# CNC-MainStepInterface-panel.net
KiCad netlist of a schematic drawn in EAGLE
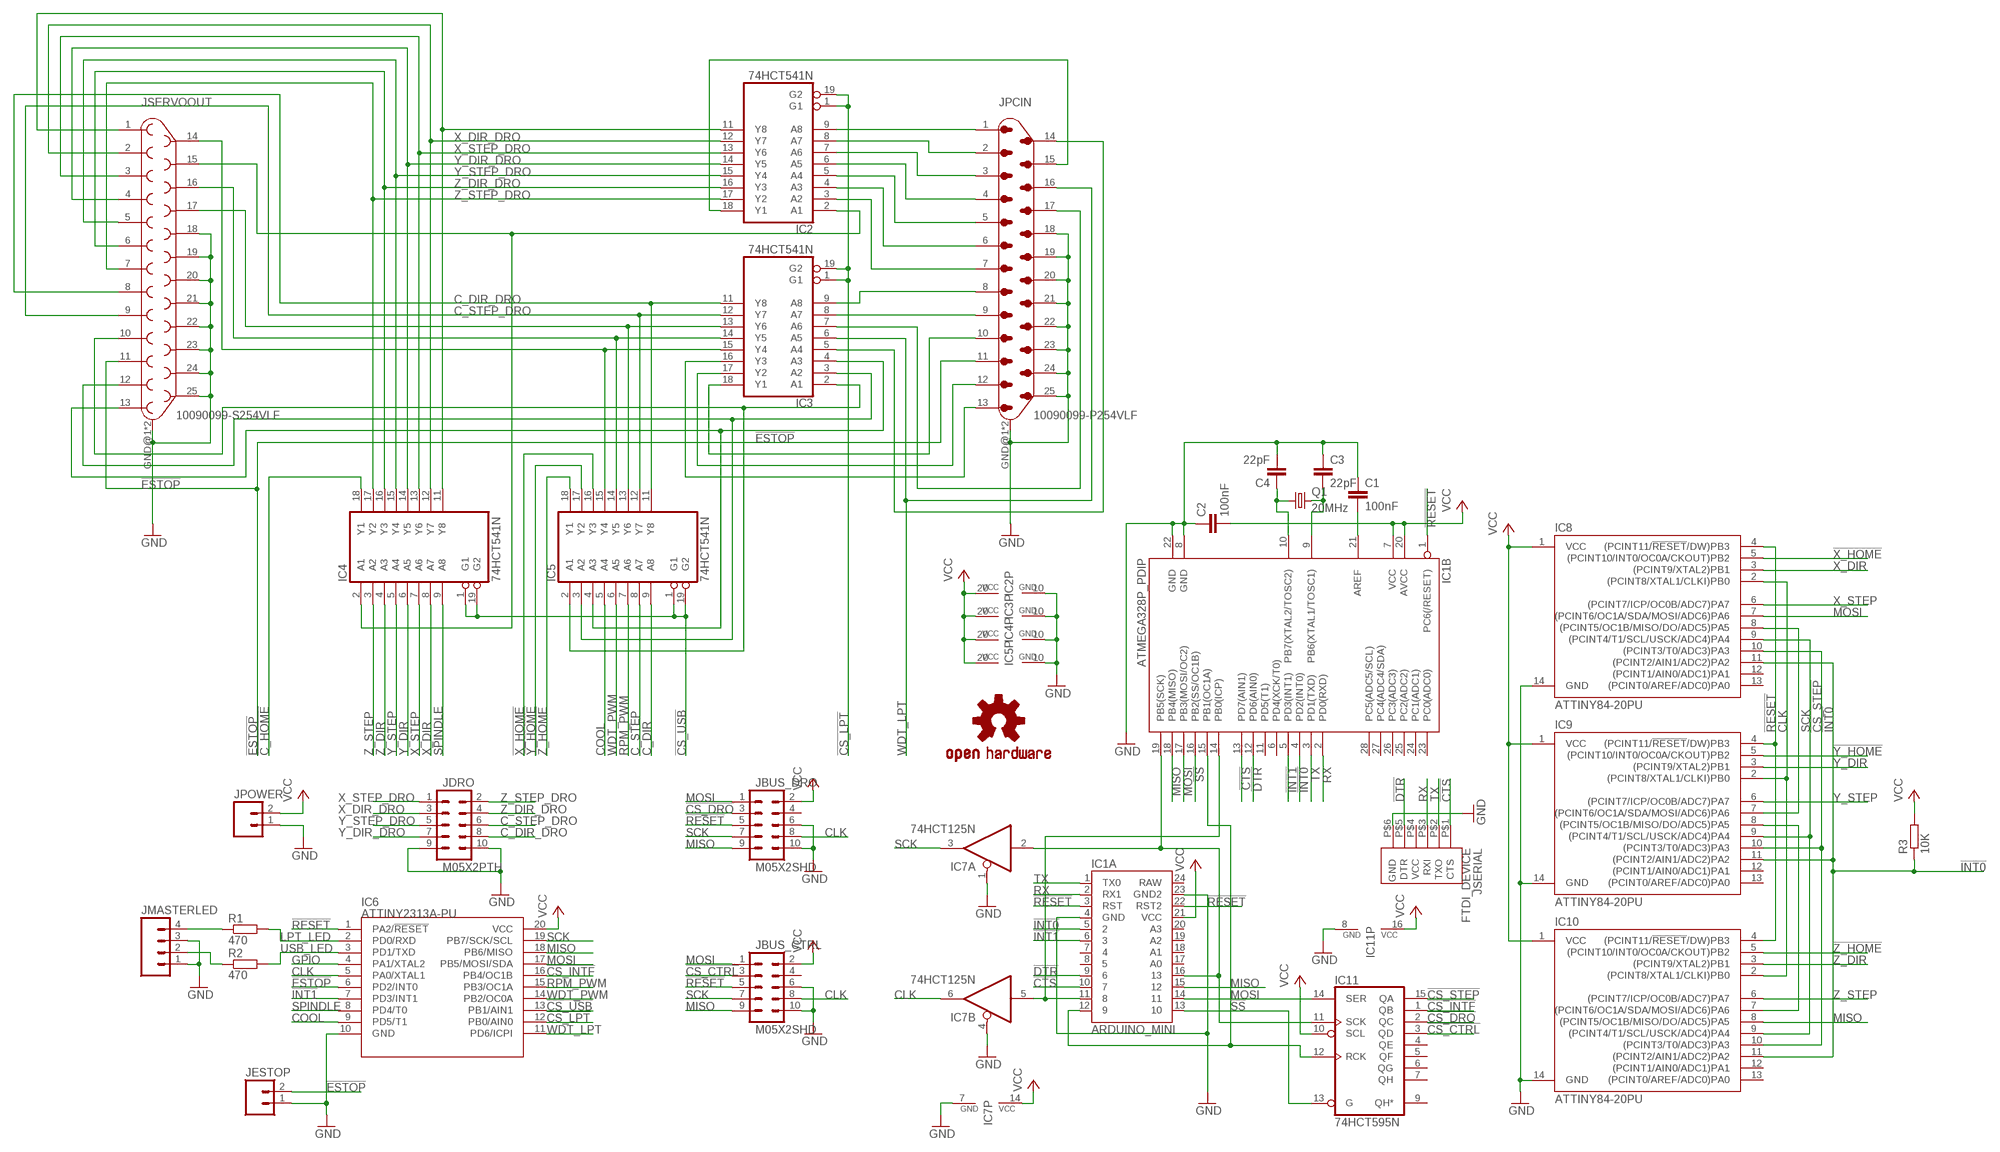
[diagram p0: schematic, sheet 1]

(export (version "E")
  (design (tool "Eeschema 10.0.6"))
  (components
    (comp (ref "C1")
      (value "100nF")
      (footprint "eagle-import:C050-025X075")
      (libsource (lib "eagle-import") (part "C-EU050-025X075"))
    )
    (comp (ref "C2")
      (value "100nF")
      (footprint "eagle-import:C050-025X075")
      (libsource (lib "eagle-import") (part "C-EU050-025X075"))
    )
    (comp (ref "C3")
      (value "22pF")
      (footprint "eagle-import:C050-025X075")
      (libsource (lib "eagle-import") (part "C-EU050-025X075"))
    )
    (comp (ref "C4")
      (value "22pF")
      (footprint "eagle-import:C050-025X075")
      (libsource (lib "eagle-import") (part "C-EU050-025X075"))
    )
    (comp (ref "IC1A")
      (value "ARDUINO_MINI")
      (footprint "eagle-import:ARDUINO_MINI")
      (libsource (lib "eagle-import") (part "ARDUINO_MINI"))
    )
    (comp (ref "IC1B")
      (value "ATMEGA328P_PDIP")
      (footprint "eagle-import:DIL28-3")
      (libsource (lib "eagle-import") (part "ATMEGA328P_PDIP"))
    )
    (comp (ref "IC2")
      (value "74HCT541N")
      (footprint "eagle-import:DIL20")
      (libsource (lib "eagle-import") (part "74541NHCT"))
    )
    (comp (ref "IC3")
      (value "74HCT541N")
      (footprint "eagle-import:DIL20")
      (libsource (lib "eagle-import") (part "74541NHCT"))
    )
    (comp (ref "IC4")
      (value "74HCT541N")
      (footprint "eagle-import:DIL20")
      (libsource (lib "eagle-import") (part "74541NHCT"))
    )
    (comp (ref "IC5")
      (value "74HCT541N")
      (footprint "eagle-import:DIL20")
      (libsource (lib "eagle-import") (part "74541NHCT"))
    )
    (comp (ref "IC6")
      (value "ATTINY2313A-PU")
      (footprint "eagle-import:DIL20")
      (libsource (lib "eagle-import") (part "ATTINY2313A-PU"))
    )
    (comp (ref "IC7")
      (value "74HCT125N")
      (footprint "eagle-import:DIL14")
      (libsource (lib "eagle-import") (part "74125NHCT"))
    )
    (comp (ref "IC8")
      (value "ATTINY84-20PU")
      (footprint "eagle-import:DIL14")
      (libsource (lib "eagle-import") (part "ATTINY84PU-20"))
    )
    (comp (ref "IC9")
      (value "ATTINY84-20PU")
      (footprint "eagle-import:DIL14")
      (libsource (lib "eagle-import") (part "ATTINY84PU-20"))
    )
    (comp (ref "IC10")
      (value "ATTINY84-20PU")
      (footprint "eagle-import:DIL14")
      (libsource (lib "eagle-import") (part "ATTINY84PU-20"))
    )
    (comp (ref "IC11")
      (value "74HCT595N")
      (footprint "eagle-import:DIL16")
      (libsource (lib "eagle-import") (part "74595NHCT"))
    )
    (comp (ref "JBUS_CTRL")
      (value "M05X2SHD")
      (footprint "eagle-import:2X5-SHROUDED")
      (libsource (lib "eagle-import") (part "M05X2SHD"))
    )
    (comp (ref "JBUS_DRO")
      (value "M05X2SHD")
      (footprint "eagle-import:2X5-SHROUDED")
      (libsource (lib "eagle-import") (part "M05X2SHD"))
    )
    (comp (ref "JDRO")
      (value "M05X2PTH")
      (footprint "eagle-import:AVR_ICSP")
      (libsource (lib "eagle-import") (part "M05X2PTH"))
    )
    (comp (ref "JESTOP")
      (value "M02PTH")
      (footprint "eagle-import:1X02")
      (libsource (lib "eagle-import") (part "M02PTH"))
    )
    (comp (ref "JMASTERLED")
      (value "M04PTH")
      (footprint "eagle-import:1X04")
      (libsource (lib "eagle-import") (part "M04PTH"))
    )
    (comp (ref "JPCIN")
      (value "10090099-P254VLF")
      (footprint "eagle-import:10090099-P254VLF")
      (libsource (lib "eagle-import") (part "10090099-P254VLF"))
    )
    (comp (ref "JPOWER")
      (value "M02POLAR")
      (footprint "eagle-import:MOLEX-1X2")
      (libsource (lib "eagle-import") (part "M02POLAR"))
    )
    (comp (ref "JSERIAL")
      (value "FTDI_DEVICE")
      (footprint "eagle-import:FTDI_DEVICE_SIDE")
      (libsource (lib "eagle-import") (part "FTDI_DEVICE"))
    )
    (comp (ref "JSERVOOUT")
      (value "10090099-S254VLF")
      (footprint "eagle-import:10090099-S254VLF")
      (libsource (lib "eagle-import") (part "10090099-S254VLF"))
    )
    (comp (ref "Q1")
      (value "20MHz")
      (footprint "eagle-import:HC49U-V")
      (libsource (lib "eagle-import") (part "CRYSTALHC49U-V"))
    )
    (comp (ref "R1")
      (value "470")
      (footprint "eagle-import:0207_10")
      (libsource (lib "eagle-import") (part "R-EU_0207/10"))
    )
    (comp (ref "R2")
      (value "470")
      (footprint "eagle-import:0207_10")
      (libsource (lib "eagle-import") (part "R-EU_0207/10"))
    )
    (comp (ref "R3")
      (value "10K")
      (footprint "eagle-import:0207_10")
      (libsource (lib "eagle-import") (part "R-EU_0207/10"))
    )
    (comp (ref "U$1")
      (value "SPARKFUN_OSHW-LOGOL")
      (footprint "eagle-import:SPARKFUN_OSHW-LOGO-L")
      (libsource (lib "eagle-import") (part "SPARKFUN_OSHW-LOGOL"))
    )
  )
  (nets
    (net (code "1") (name "/CLK") (class "Default")
      (node (ref "IC10") (pin "2") (pinfunction "(PCINT8/XTAL1/CLKI)PB0_2") (pintype "bidirectional"))
      (node (ref "IC6") (pin "5") (pinfunction "PA0/XTAL1_5") (pintype "bidirectional"))
      (node (ref "IC7") (pin "6") (pinfunction "O_6") (pintype "tri_state"))
      (node (ref "IC8") (pin "2") (pinfunction "(PCINT8/XTAL1/CLKI)PB0_2") (pintype "bidirectional"))
      (node (ref "IC9") (pin "2") (pinfunction "(PCINT8/XTAL1/CLKI)PB0_2") (pintype "bidirectional"))
      (node (ref "JBUS_CTRL") (pin "8") (pinfunction "8_8") (pintype "passive"))
      (node (ref "JBUS_DRO") (pin "8") (pinfunction "8_8") (pintype "passive"))
    )
    (net (code "2") (name "/COOL") (class "Default")
      (node (ref "IC5") (pin "5") (pinfunction "A4_5") (pintype "input"))
      (node (ref "IC6") (pin "9") (pinfunction "PD5/T1_9") (pintype "bidirectional"))
    )
    (net (code "3") (name "/C_DIR") (class "Default")
      (node (ref "IC5") (pin "9") (pinfunction "A8_9") (pintype "input"))
    )
    (net (code "4") (name "/C_DIR_DRO") (class "Default")
      (node (ref "IC3") (pin "11") (pinfunction "Y8_11") (pintype "tri_state"))
      (node (ref "IC5") (pin "11") (pinfunction "Y8_11") (pintype "tri_state"))
      (node (ref "JDRO") (pin "8") (pinfunction "8_8") (pintype "passive"))
      (node (ref "JSERVOOUT") (pin "8") (pinfunction "8_8") (pintype "passive"))
    )
    (net (code "5") (name "/C_STEP") (class "Default")
      (node (ref "IC5") (pin "8") (pinfunction "A7_8") (pintype "input"))
    )
    (net (code "6") (name "/C_STEP_DRO") (class "Default")
      (node (ref "IC3") (pin "12") (pinfunction "Y7_12") (pintype "tri_state"))
      (node (ref "IC5") (pin "12") (pinfunction "Y7_12") (pintype "tri_state"))
      (node (ref "JDRO") (pin "6") (pinfunction "6_6") (pintype "passive"))
      (node (ref "JSERVOOUT") (pin "9") (pinfunction "9_9") (pintype "passive"))
    )
    (net (code "7") (name "/GPIO") (class "Default")
      (node (ref "IC6") (pin "4") (pinfunction "PA1/XTAL2_4") (pintype "bidirectional"))
    )
    (net (code "8") (name "/LPT_LED") (class "Default")
      (node (ref "IC6") (pin "2") (pinfunction "PD0/RXD_2") (pintype "bidirectional"))
      (node (ref "R1") (pin "2") (pinfunction "2_2") (pintype "passive"))
    )
    (net (code "9") (name "/MISO") (class "Default")
      (node (ref "IC10") (pin "8") (pinfunction "(PCINT5/OC1B/MISO/DO/ADC5)PA5_8") (pintype "bidirectional"))
      (node (ref "IC1A") (pin "15") (pinfunction "12_15") (pintype "bidirectional"))
      (node (ref "IC1B") (pin "18") (pinfunction "PB4(MISO)_18") (pintype "bidirectional"))
      (node (ref "IC6") (pin "18") (pinfunction "PB6/MISO_18") (pintype "bidirectional"))
      (node (ref "JBUS_CTRL") (pin "9") (pinfunction "9_9") (pintype "passive"))
      (node (ref "JBUS_DRO") (pin "9") (pinfunction "9_9") (pintype "passive"))
    )
    (net (code "10") (name "/MOSI") (class "Default")
      (node (ref "IC11") (pin "14") (pinfunction "SER_14") (pintype "input"))
      (node (ref "IC1A") (pin "14") (pinfunction "11_14") (pintype "bidirectional"))
      (node (ref "IC1B") (pin "17") (pinfunction "PB3(MOSI/OC2)_17") (pintype "bidirectional"))
      (node (ref "IC6") (pin "17") (pinfunction "PB5/MOSI/SDA_17") (pintype "bidirectional"))
      (node (ref "IC8") (pin "7") (pinfunction "(PCINT6/OC1A/SDA/MOSI/ADC6)PA6_7") (pintype "bidirectional"))
      (node (ref "JBUS_CTRL") (pin "1") (pinfunction "1_1") (pintype "passive"))
      (node (ref "JBUS_DRO") (pin "1") (pinfunction "1_1") (pintype "passive"))
    )
    (net (code "11") (name "/RPM_PWM") (class "Default")
      (node (ref "IC5") (pin "7") (pinfunction "A6_7") (pintype "input"))
      (node (ref "IC6") (pin "15") (pinfunction "PB3/OC1A_15") (pintype "bidirectional"))
    )
    (net (code "12") (name "/RX") (class "Default")
      (node (ref "IC1A") (pin "2") (pinfunction "RX1_2") (pintype "bidirectional"))
      (node (ref "IC1B") (pin "2") (pinfunction "PD0(RXD)_2") (pintype "bidirectional"))
      (node (ref "JSERIAL") (pin "P$3") (pinfunction "RXI_P$3") (pintype "bidirectional"))
    )
    (net (code "13") (name "/SCK") (class "Default")
      (node (ref "IC10") (pin "9") (pinfunction "(PCINT4/T1/SCL/USCK/ADC4)PA4_9") (pintype "bidirectional"))
      (node (ref "IC6") (pin "19") (pinfunction "PB7/SCK/SCL_19") (pintype "bidirectional"))
      (node (ref "IC7") (pin "3") (pinfunction "O_3") (pintype "tri_state"))
      (node (ref "IC8") (pin "9") (pinfunction "(PCINT4/T1/SCL/USCK/ADC4)PA4_9") (pintype "bidirectional"))
      (node (ref "IC9") (pin "9") (pinfunction "(PCINT4/T1/SCL/USCK/ADC4)PA4_9") (pintype "bidirectional"))
      (node (ref "JBUS_CTRL") (pin "7") (pinfunction "7_7") (pintype "passive"))
      (node (ref "JBUS_DRO") (pin "7") (pinfunction "7_7") (pintype "passive"))
    )
    (net (code "14") (name "/SPINDLE") (class "Default")
      (node (ref "IC4") (pin "9") (pinfunction "A8_9") (pintype "input"))
      (node (ref "IC6") (pin "8") (pinfunction "PD4/T0_8") (pintype "bidirectional"))
    )
    (net (code "15") (name "/TX") (class "Default")
      (node (ref "IC1A") (pin "1") (pinfunction "TX0_1") (pintype "bidirectional"))
      (node (ref "IC1B") (pin "3") (pinfunction "PD1(TXD)_3") (pintype "bidirectional"))
      (node (ref "JSERIAL") (pin "P$2") (pinfunction "TXO_P$2") (pintype "bidirectional"))
    )
    (net (code "16") (name "/USB_LED") (class "Default")
      (node (ref "IC6") (pin "3") (pinfunction "PD1/TXD_3") (pintype "bidirectional"))
      (node (ref "R2") (pin "2") (pinfunction "2_2") (pintype "passive"))
    )
    (net (code "17") (name "/WDT_LPT") (class "Default")
      (node (ref "IC3") (pin "6") (pinfunction "A5_6") (pintype "input"))
      (node (ref "IC6") (pin "11") (pinfunction "PD6/ICPI_11") (pintype "bidirectional"))
      (node (ref "JPCIN") (pin "16") (pinfunction "16_16") (pintype "passive"))
    )
    (net (code "18") (name "/WDT_PWM") (class "Default")
      (node (ref "IC5") (pin "6") (pinfunction "A5_6") (pintype "input"))
      (node (ref "IC6") (pin "14") (pinfunction "PB2/OC0A_14") (pintype "bidirectional"))
    )
    (net (code "19") (name "/X_DIR") (class "Default")
      (node (ref "IC4") (pin "8") (pinfunction "A7_8") (pintype "input"))
      (node (ref "IC8") (pin "3") (pinfunction "(PCINT9/XTAL2)PB1_3") (pintype "bidirectional"))
    )
    (net (code "20") (name "/X_DIR_DRO") (class "Default")
      (node (ref "IC2") (pin "12") (pinfunction "Y7_12") (pintype "tri_state"))
      (node (ref "IC4") (pin "12") (pinfunction "Y7_12") (pintype "tri_state"))
      (node (ref "JDRO") (pin "3") (pinfunction "3_3") (pintype "passive"))
      (node (ref "JSERVOOUT") (pin "2") (pinfunction "2_2") (pintype "passive"))
    )
    (net (code "21") (name "/X_STEP") (class "Default")
      (node (ref "IC4") (pin "7") (pinfunction "A6_7") (pintype "input"))
      (node (ref "IC8") (pin "6") (pinfunction "(PCINT7/ICP/OC0B/ADC7)PA7_6") (pintype "bidirectional"))
    )
    (net (code "22") (name "/X_STEP_DRO") (class "Default")
      (node (ref "IC2") (pin "13") (pinfunction "Y6_13") (pintype "tri_state"))
      (node (ref "IC4") (pin "13") (pinfunction "Y6_13") (pintype "tri_state"))
      (node (ref "JDRO") (pin "1") (pinfunction "1_1") (pintype "passive"))
      (node (ref "JSERVOOUT") (pin "3") (pinfunction "3_3") (pintype "passive"))
    )
    (net (code "23") (name "/Y_DIR") (class "Default")
      (node (ref "IC4") (pin "6") (pinfunction "A5_6") (pintype "input"))
      (node (ref "IC9") (pin "3") (pinfunction "(PCINT9/XTAL2)PB1_3") (pintype "bidirectional"))
    )
    (net (code "24") (name "/Y_DIR_DRO") (class "Default")
      (node (ref "IC2") (pin "14") (pinfunction "Y5_14") (pintype "tri_state"))
      (node (ref "IC4") (pin "14") (pinfunction "Y5_14") (pintype "tri_state"))
      (node (ref "JDRO") (pin "7") (pinfunction "7_7") (pintype "passive"))
      (node (ref "JSERVOOUT") (pin "4") (pinfunction "4_4") (pintype "passive"))
    )
    (net (code "25") (name "/Y_STEP") (class "Default")
      (node (ref "IC4") (pin "5") (pinfunction "A4_5") (pintype "input"))
      (node (ref "IC9") (pin "6") (pinfunction "(PCINT7/ICP/OC0B/ADC7)PA7_6") (pintype "bidirectional"))
    )
    (net (code "26") (name "/Y_STEP_DRO") (class "Default")
      (node (ref "IC2") (pin "15") (pinfunction "Y4_15") (pintype "tri_state"))
      (node (ref "IC4") (pin "15") (pinfunction "Y4_15") (pintype "tri_state"))
      (node (ref "JDRO") (pin "5") (pinfunction "5_5") (pintype "passive"))
      (node (ref "JSERVOOUT") (pin "5") (pinfunction "5_5") (pintype "passive"))
    )
    (net (code "27") (name "/Z_DIR") (class "Default")
      (node (ref "IC10") (pin "3") (pinfunction "(PCINT9/XTAL2)PB1_3") (pintype "bidirectional"))
      (node (ref "IC4") (pin "4") (pinfunction "A3_4") (pintype "input"))
    )
    (net (code "28") (name "/Z_DIR_DRO") (class "Default")
      (node (ref "IC2") (pin "16") (pinfunction "Y3_16") (pintype "tri_state"))
      (node (ref "IC4") (pin "16") (pinfunction "Y3_16") (pintype "tri_state"))
      (node (ref "JDRO") (pin "4") (pinfunction "4_4") (pintype "passive"))
      (node (ref "JSERVOOUT") (pin "6") (pinfunction "6_6") (pintype "passive"))
    )
    (net (code "29") (name "/Z_STEP") (class "Default")
      (node (ref "IC10") (pin "6") (pinfunction "(PCINT7/ICP/OC0B/ADC7)PA7_6") (pintype "bidirectional"))
      (node (ref "IC4") (pin "3") (pinfunction "A2_3") (pintype "input"))
    )
    (net (code "30") (name "/Z_STEP_DRO") (class "Default")
      (node (ref "IC2") (pin "17") (pinfunction "Y2_17") (pintype "tri_state"))
      (node (ref "IC4") (pin "17") (pinfunction "Y2_17") (pintype "tri_state"))
      (node (ref "JDRO") (pin "2") (pinfunction "2_2") (pintype "passive"))
      (node (ref "JSERVOOUT") (pin "7") (pinfunction "7_7") (pintype "passive"))
    )
    (net (code "31") (name "/~{CS_CTRL}") (class "Default")
      (node (ref "IC11") (pin "3") (pinfunction "QD_3") (pintype "tri_state"))
      (node (ref "JBUS_CTRL") (pin "3") (pinfunction "3_3") (pintype "passive"))
    )
    (net (code "32") (name "/~{CS_DRO}") (class "Default")
      (node (ref "IC11") (pin "2") (pinfunction "QC_2") (pintype "tri_state"))
      (node (ref "JBUS_DRO") (pin "3") (pinfunction "3_3") (pintype "passive"))
    )
    (net (code "33") (name "/~{CS_INTF}") (class "Default")
      (node (ref "IC11") (pin "1") (pinfunction "QB_1") (pintype "tri_state"))
      (node (ref "IC6") (pin "16") (pinfunction "PB4/OC1B_16") (pintype "bidirectional"))
    )
    (net (code "34") (name "/~{CS_LPT}") (class "Default")
      (node (ref "IC2") (pin "1") (pinfunction "G1_1") (pintype "input"))
      (node (ref "IC2") (pin "19") (pinfunction "G2_19") (pintype "input"))
      (node (ref "IC3") (pin "1") (pinfunction "G1_1") (pintype "input"))
      (node (ref "IC3") (pin "19") (pinfunction "G2_19") (pintype "input"))
      (node (ref "IC6") (pin "12") (pinfunction "PB0/AIN0_12") (pintype "bidirectional"))
    )
    (net (code "35") (name "/~{CS_STEP}") (class "Default")
      (node (ref "IC10") (pin "10") (pinfunction "(PCINT3/T0/ADC3)PA3_10") (pintype "bidirectional"))
      (node (ref "IC11") (pin "15") (pinfunction "QA_15") (pintype "tri_state"))
      (node (ref "IC8") (pin "10") (pinfunction "(PCINT3/T0/ADC3)PA3_10") (pintype "bidirectional"))
      (node (ref "IC9") (pin "10") (pinfunction "(PCINT3/T0/ADC3)PA3_10") (pintype "bidirectional"))
    )
    (net (code "36") (name "/~{CS_USB}") (class "Default")
      (node (ref "IC4") (pin "1") (pinfunction "G1_1") (pintype "input"))
      (node (ref "IC4") (pin "19") (pinfunction "G2_19") (pintype "input"))
      (node (ref "IC5") (pin "1") (pinfunction "G1_1") (pintype "input"))
      (node (ref "IC5") (pin "19") (pinfunction "G2_19") (pintype "input"))
      (node (ref "IC6") (pin "13") (pinfunction "PB1/AIN1_13") (pintype "bidirectional"))
    )
    (net (code "37") (name "/~{CTS}") (class "Default")
      (node (ref "IC1A") (pin "10") (pinfunction "7_10") (pintype "bidirectional"))
      (node (ref "IC1B") (pin "13") (pinfunction "PD7(AIN1)_13") (pintype "bidirectional"))
      (node (ref "JSERIAL") (pin "P$1") (pinfunction "CTS_P$1") (pintype "bidirectional"))
    )
    (net (code "38") (name "/~{C_HOME}") (class "Default")
      (node (ref "IC4") (pin "18") (pinfunction "Y1_18") (pintype "tri_state"))
    )
    (net (code "39") (name "/~{DTR}") (class "Default")
      (node (ref "IC1A") (pin "9") (pinfunction "6_9") (pintype "bidirectional"))
      (node (ref "IC1B") (pin "12") (pinfunction "PD6(AIN0)_12") (pintype "bidirectional"))
      (node (ref "JSERIAL") (pin "P$5") (pinfunction "DTR_P$5") (pintype "bidirectional"))
    )
    (net (code "40") (name "/~{ESTOP}") (class "Default")
      (node (ref "IC6") (pin "6") (pinfunction "PD2/INT0_6") (pintype "bidirectional"))
      (node (ref "JESTOP") (pin "2") (pinfunction "2_2") (pintype "passive"))
      (node (ref "JPCIN") (pin "11") (pinfunction "11_11") (pintype "passive"))
      (node (ref "JSERVOOUT") (pin "11") (pinfunction "11_11") (pintype "passive"))
    )
    (net (code "41") (name "/~{INT0}") (class "Default")
      (node (ref "IC10") (pin "11") (pinfunction "(PCINT2/AIN1/ADC2)PA2_11") (pintype "bidirectional"))
      (node (ref "IC1A") (pin "5") (pinfunction "2_5") (pintype "bidirectional"))
      (node (ref "IC1B") (pin "4") (pinfunction "PD2(INT0)_4") (pintype "bidirectional"))
      (node (ref "IC8") (pin "11") (pinfunction "(PCINT2/AIN1/ADC2)PA2_11") (pintype "bidirectional"))
      (node (ref "IC9") (pin "11") (pinfunction "(PCINT2/AIN1/ADC2)PA2_11") (pintype "bidirectional"))
      (node (ref "R3") (pin "1") (pinfunction "1_1") (pintype "passive"))
    )
    (net (code "42") (name "/~{INT1}") (class "Default")
      (node (ref "IC1A") (pin "6") (pinfunction "3_6") (pintype "bidirectional"))
      (node (ref "IC1B") (pin "5") (pinfunction "PD3(INT1)_5") (pintype "bidirectional"))
      (node (ref "IC6") (pin "7") (pinfunction "PD3/INT1_7") (pintype "bidirectional"))
    )
    (net (code "43") (name "/~{RESET}") (class "Default")
      (node (ref "IC10") (pin "4") (pinfunction "(PCINT11/~{RESET}/DW)PB3_4") (pintype "bidirectional"))
      (node (ref "IC1A") (pin "22") (pinfunction "RST2_22") (pintype "bidirectional"))
      (node (ref "IC1A") (pin "3") (pinfunction "RST_3") (pintype "bidirectional"))
      (node (ref "IC1B") (pin "1") (pinfunction "PC6(/RESET)_1") (pintype "bidirectional"))
      (node (ref "IC6") (pin "1") (pinfunction "PA2/~{RESET}_1") (pintype "bidirectional"))
      (node (ref "IC8") (pin "4") (pinfunction "(PCINT11/~{RESET}/DW)PB3_4") (pintype "bidirectional"))
      (node (ref "IC9") (pin "4") (pinfunction "(PCINT11/~{RESET}/DW)PB3_4") (pintype "bidirectional"))
      (node (ref "JBUS_CTRL") (pin "5") (pinfunction "5_5") (pintype "passive"))
      (node (ref "JBUS_DRO") (pin "5") (pinfunction "5_5") (pintype "passive"))
    )
    (net (code "44") (name "/~{SS}") (class "Default")
      (node (ref "IC11") (pin "13") (pinfunction "G_13") (pintype "input"))
      (node (ref "IC1A") (pin "13") (pinfunction "10_13") (pintype "bidirectional"))
      (node (ref "IC1B") (pin "16") (pinfunction "PB2(SS/OC1B)_16") (pintype "bidirectional"))
    )
    (net (code "45") (name "/~{X_HOME}") (class "Default")
      (node (ref "IC5") (pin "16") (pinfunction "Y3_16") (pintype "tri_state"))
      (node (ref "IC8") (pin "5") (pinfunction "(PCINT10/INT0/OC0A/CKOUT)PB2_5") (pintype "bidirectional"))
    )
    (net (code "46") (name "/~{Y_HOME}") (class "Default")
      (node (ref "IC5") (pin "17") (pinfunction "Y2_17") (pintype "tri_state"))
      (node (ref "IC9") (pin "5") (pinfunction "(PCINT10/INT0/OC0A/CKOUT)PB2_5") (pintype "bidirectional"))
    )
    (net (code "47") (name "/~{Z_HOME}") (class "Default")
      (node (ref "IC10") (pin "5") (pinfunction "(PCINT10/INT0/OC0A/CKOUT)PB2_5") (pintype "bidirectional"))
      (node (ref "IC5") (pin "18") (pinfunction "Y1_18") (pintype "tri_state"))
    )
    (net (code "48") (name "GND") (class "Default")
      (node (ref "C1") (pin "1") (pinfunction "1_1") (pintype "passive"))
      (node (ref "C2") (pin "1") (pinfunction "1_1") (pintype "passive"))
      (node (ref "C3") (pin "1") (pinfunction "1_1") (pintype "passive"))
      (node (ref "C4") (pin "2") (pinfunction "2_2") (pintype "passive"))
      (node (ref "IC10") (pin "14") (pinfunction "GND_14") (pintype "bidirectional"))
      (node (ref "IC11") (pin "8") (pinfunction "GND_8") (pintype "power_in"))
      (node (ref "IC1A") (pin "23") (pinfunction "GND2_23") (pintype "bidirectional"))
      (node (ref "IC1A") (pin "4") (pinfunction "GND_4") (pintype "bidirectional"))
      (node (ref "IC1B") (pin "22") (pinfunction "GND_22") (pintype "bidirectional"))
      (node (ref "IC1B") (pin "8") (pinfunction "GND_8") (pintype "bidirectional"))
      (node (ref "IC2") (pin "10") (pinfunction "GND_10") (pintype "power_in"))
      (node (ref "IC3") (pin "10") (pinfunction "GND_10") (pintype "power_in"))
      (node (ref "IC4") (pin "10") (pinfunction "GND_10") (pintype "power_in"))
      (node (ref "IC5") (pin "10") (pinfunction "GND_10") (pintype "power_in"))
      (node (ref "IC6") (pin "10") (pinfunction "GND_10") (pintype "bidirectional"))
      (node (ref "IC7") (pin "1") (pinfunction "OE_1") (pintype "input"))
      (node (ref "IC7") (pin "4") (pinfunction "OE_4") (pintype "input"))
      (node (ref "IC7") (pin "7") (pinfunction "GND_7") (pintype "power_in"))
      (node (ref "IC8") (pin "14") (pinfunction "GND_14") (pintype "bidirectional"))
      (node (ref "IC9") (pin "14") (pinfunction "GND_14") (pintype "bidirectional"))
      (node (ref "JBUS_CTRL") (pin "10") (pinfunction "10_10") (pintype "passive"))
      (node (ref "JBUS_CTRL") (pin "6") (pinfunction "6_6") (pintype "passive"))
      (node (ref "JBUS_DRO") (pin "10") (pinfunction "10_10") (pintype "passive"))
      (node (ref "JBUS_DRO") (pin "6") (pinfunction "6_6") (pintype "passive"))
      (node (ref "JDRO") (pin "10") (pinfunction "10_10") (pintype "passive"))
      (node (ref "JDRO") (pin "9") (pinfunction "9_9") (pintype "passive"))
      (node (ref "JESTOP") (pin "1") (pinfunction "1_1") (pintype "passive"))
      (node (ref "JMASTERLED") (pin "1") (pinfunction "1_1") (pintype "passive"))
      (node (ref "JMASTERLED") (pin "3") (pinfunction "3_3") (pintype "passive"))
      (node (ref "JPCIN") (pin "18") (pinfunction "18_18") (pintype "passive"))
      (node (ref "JPCIN") (pin "19") (pinfunction "19_19") (pintype "passive"))
      (node (ref "JPCIN") (pin "20") (pinfunction "20_20") (pintype "passive"))
      (node (ref "JPCIN") (pin "21") (pinfunction "21_21") (pintype "passive"))
      (node (ref "JPCIN") (pin "22") (pinfunction "22_22") (pintype "passive"))
      (node (ref "JPCIN") (pin "23") (pinfunction "23_23") (pintype "passive"))
      (node (ref "JPCIN") (pin "24") (pinfunction "24_24") (pintype "passive"))
      (node (ref "JPCIN") (pin "25") (pinfunction "25_25") (pintype "passive"))
      (node (ref "JPCIN") (pin "GND@1") (pinfunction "GND_GND@1") (pintype "power_in"))
      (node (ref "JPCIN") (pin "GND@2") (pinfunction "GND_GND@2") (pintype "power_in"))
      (node (ref "JPOWER") (pin "1") (pinfunction "1_1") (pintype "passive"))
      (node (ref "JSERIAL") (pin "P$6") (pinfunction "GND_P$6") (pintype "bidirectional"))
      (node (ref "JSERVOOUT") (pin "18") (pinfunction "18_18") (pintype "passive"))
      (node (ref "JSERVOOUT") (pin "19") (pinfunction "19_19") (pintype "passive"))
      (node (ref "JSERVOOUT") (pin "20") (pinfunction "20_20") (pintype "passive"))
      (node (ref "JSERVOOUT") (pin "21") (pinfunction "21_21") (pintype "passive"))
      (node (ref "JSERVOOUT") (pin "22") (pinfunction "22_22") (pintype "passive"))
      (node (ref "JSERVOOUT") (pin "23") (pinfunction "23_23") (pintype "passive"))
      (node (ref "JSERVOOUT") (pin "24") (pinfunction "24_24") (pintype "passive"))
      (node (ref "JSERVOOUT") (pin "25") (pinfunction "25_25") (pintype "passive"))
      (node (ref "JSERVOOUT") (pin "GND@1") (pinfunction "GND_GND@1") (pintype "power_in"))
      (node (ref "JSERVOOUT") (pin "GND@2") (pinfunction "GND_GND@2") (pintype "power_in"))
    )
    (net (code "49") (name "Net-(IC1A-8)") (class "Default")
      (node (ref "IC1A") (pin "11") (pinfunction "8_11") (pintype "bidirectional"))
      (node (ref "IC1B") (pin "14") (pinfunction "PB0(ICP)_14") (pintype "bidirectional"))
      (node (ref "IC7") (pin "5") (pinfunction "I_5") (pintype "input"))
    )
    (net (code "50") (name "Net-(IC1B-AREF)") (class "Default")
      (node (ref "C1") (pin "2") (pinfunction "2_2") (pintype "passive"))
      (node (ref "IC1B") (pin "21") (pinfunction "AREF_21") (pintype "bidirectional"))
    )
    (net (code "51") (name "Net-(IC1B-PB6(XTAL1{slash}TOSC1))") (class "Default")
      (node (ref "C3") (pin "2") (pinfunction "2_2") (pintype "passive"))
      (node (ref "IC1B") (pin "9") (pinfunction "PB6(XTAL1/TOSC1)_9") (pintype "bidirectional"))
      (node (ref "Q1") (pin "2") (pinfunction "2_2") (pintype "passive"))
    )
    (net (code "52") (name "Net-(IC1B-PB7(XTAL2{slash}TOSC2))") (class "Default")
      (node (ref "C4") (pin "1") (pinfunction "1_1") (pintype "passive"))
      (node (ref "IC1B") (pin "10") (pinfunction "PB7(XTAL2/TOSC2)_10") (pintype "bidirectional"))
      (node (ref "Q1") (pin "1") (pinfunction "1_1") (pintype "passive"))
    )
    (net (code "53") (name "Net-(IC2A-A1)") (class "Default")
      (node (ref "IC2") (pin "2") (pinfunction "A1_2") (pintype "input"))
      (node (ref "IC4") (pin "2") (pinfunction "A1_2") (pintype "input"))
      (node (ref "JSERVOOUT") (pin "15") (pinfunction "15_15") (pintype "passive"))
    )
    (net (code "54") (name "Net-(IC2A-A2)") (class "Default")
      (node (ref "IC2") (pin "3") (pinfunction "A2_3") (pintype "input"))
      (node (ref "JPCIN") (pin "7") (pinfunction "7_7") (pintype "passive"))
    )
    (net (code "55") (name "Net-(IC2A-A3)") (class "Default")
      (node (ref "IC2") (pin "4") (pinfunction "A3_4") (pintype "input"))
      (node (ref "JPCIN") (pin "6") (pinfunction "6_6") (pintype "passive"))
    )
    (net (code "56") (name "Net-(IC2A-A4)") (class "Default")
      (node (ref "IC2") (pin "5") (pinfunction "A4_5") (pintype "input"))
      (node (ref "JPCIN") (pin "5") (pinfunction "5_5") (pintype "passive"))
    )
    (net (code "57") (name "Net-(IC2A-A5)") (class "Default")
      (node (ref "IC2") (pin "6") (pinfunction "A5_6") (pintype "input"))
      (node (ref "JPCIN") (pin "4") (pinfunction "4_4") (pintype "passive"))
    )
    (net (code "58") (name "Net-(IC2A-A6)") (class "Default")
      (node (ref "IC2") (pin "7") (pinfunction "A6_7") (pintype "input"))
      (node (ref "JPCIN") (pin "3") (pinfunction "3_3") (pintype "passive"))
    )
    (net (code "59") (name "Net-(IC2A-A7)") (class "Default")
      (node (ref "IC2") (pin "8") (pinfunction "A7_8") (pintype "input"))
      (node (ref "JPCIN") (pin "2") (pinfunction "2_2") (pintype "passive"))
    )
    (net (code "60") (name "Net-(IC2A-A8)") (class "Default")
      (node (ref "IC2") (pin "9") (pinfunction "A8_9") (pintype "input"))
      (node (ref "JPCIN") (pin "1") (pinfunction "1_1") (pintype "passive"))
    )
    (net (code "61") (name "Net-(IC2A-Y1)") (class "Default")
      (node (ref "IC2") (pin "18") (pinfunction "Y1_18") (pintype "tri_state"))
      (node (ref "JPCIN") (pin "15") (pinfunction "15_15") (pintype "passive"))
    )
    (net (code "62") (name "Net-(IC2A-Y8)") (class "Default")
      (node (ref "IC2") (pin "11") (pinfunction "Y8_11") (pintype "tri_state"))
      (node (ref "IC4") (pin "11") (pinfunction "Y8_11") (pintype "tri_state"))
      (node (ref "JSERVOOUT") (pin "1") (pinfunction "1_1") (pintype "passive"))
    )
    (net (code "63") (name "Net-(IC3A-A1)") (class "Default")
      (node (ref "IC3") (pin "2") (pinfunction "A1_2") (pintype "input"))
      (node (ref "IC5") (pin "2") (pinfunction "A1_2") (pintype "input"))
      (node (ref "JSERVOOUT") (pin "10") (pinfunction "10_10") (pintype "passive"))
    )
    (net (code "64") (name "Net-(IC3A-A2)") (class "Default")
      (node (ref "IC3") (pin "3") (pinfunction "A2_3") (pintype "input"))
      (node (ref "IC5") (pin "3") (pinfunction "A2_3") (pintype "input"))
      (node (ref "JSERVOOUT") (pin "12") (pinfunction "12_12") (pintype "passive"))
    )
    (net (code "65") (name "Net-(IC3A-A3)") (class "Default")
      (node (ref "IC3") (pin "4") (pinfunction "A3_4") (pintype "input"))
      (node (ref "IC5") (pin "4") (pinfunction "A3_4") (pintype "input"))
      (node (ref "JSERVOOUT") (pin "13") (pinfunction "13_13") (pintype "passive"))
    )
    (net (code "66") (name "Net-(IC3A-A4)") (class "Default")
      (node (ref "IC3") (pin "5") (pinfunction "A4_5") (pintype "input"))
      (node (ref "JPCIN") (pin "14") (pinfunction "14_14") (pintype "passive"))
    )
    (net (code "67") (name "Net-(IC3A-A6)") (class "Default")
      (node (ref "IC3") (pin "7") (pinfunction "A6_7") (pintype "input"))
      (node (ref "JPCIN") (pin "17") (pinfunction "17_17") (pintype "passive"))
    )
    (net (code "68") (name "Net-(IC3A-A7)") (class "Default")
      (node (ref "IC3") (pin "8") (pinfunction "A7_8") (pintype "input"))
      (node (ref "JPCIN") (pin "9") (pinfunction "9_9") (pintype "passive"))
    )
    (net (code "69") (name "Net-(IC3A-A8)") (class "Default")
      (node (ref "IC3") (pin "9") (pinfunction "A8_9") (pintype "input"))
      (node (ref "JPCIN") (pin "8") (pinfunction "8_8") (pintype "passive"))
    )
    (net (code "70") (name "Net-(IC3A-Y1)") (class "Default")
      (node (ref "IC3") (pin "18") (pinfunction "Y1_18") (pintype "tri_state"))
      (node (ref "JPCIN") (pin "10") (pinfunction "10_10") (pintype "passive"))
    )
    (net (code "71") (name "Net-(IC3A-Y2)") (class "Default")
      (node (ref "IC3") (pin "17") (pinfunction "Y2_17") (pintype "tri_state"))
      (node (ref "JPCIN") (pin "12") (pinfunction "12_12") (pintype "passive"))
    )
    (net (code "72") (name "Net-(IC3A-Y3)") (class "Default")
      (node (ref "IC3") (pin "16") (pinfunction "Y3_16") (pintype "tri_state"))
      (node (ref "JPCIN") (pin "13") (pinfunction "13_13") (pintype "passive"))
    )
    (net (code "73") (name "Net-(IC3A-Y4)") (class "Default")
      (node (ref "IC3") (pin "15") (pinfunction "Y4_15") (pintype "tri_state"))
      (node (ref "IC5") (pin "15") (pinfunction "Y4_15") (pintype "tri_state"))
      (node (ref "JSERVOOUT") (pin "14") (pinfunction "14_14") (pintype "passive"))
    )
    (net (code "74") (name "Net-(IC3A-Y5)") (class "Default")
      (node (ref "IC3") (pin "14") (pinfunction "Y5_14") (pintype "tri_state"))
      (node (ref "IC5") (pin "14") (pinfunction "Y5_14") (pintype "tri_state"))
      (node (ref "JSERVOOUT") (pin "16") (pinfunction "16_16") (pintype "passive"))
    )
    (net (code "75") (name "Net-(IC3A-Y6)") (class "Default")
      (node (ref "IC3") (pin "13") (pinfunction "Y6_13") (pintype "tri_state"))
      (node (ref "IC5") (pin "13") (pinfunction "Y6_13") (pintype "tri_state"))
      (node (ref "JSERVOOUT") (pin "17") (pinfunction "17_17") (pintype "passive"))
    )
    (net (code "76") (name "Net-(IC8-(PCINT5{slash}OC1B{slash}MISO{slash}DO{slash}ADC5)PA5)") (class "Default")
      (node (ref "IC8") (pin "8") (pinfunction "(PCINT5/OC1B/MISO/DO/ADC5)PA5_8") (pintype "bidirectional"))
      (node (ref "IC9") (pin "7") (pinfunction "(PCINT6/OC1A/SDA/MOSI/ADC6)PA6_7") (pintype "bidirectional"))
    )
    (net (code "77") (name "Net-(IC10-(PCINT6{slash}OC1A{slash}SDA{slash}MOSI{slash}ADC6)PA6)") (class "Default")
      (node (ref "IC10") (pin "7") (pinfunction "(PCINT6/OC1A/SDA/MOSI/ADC6)PA6_7") (pintype "bidirectional"))
      (node (ref "IC9") (pin "8") (pinfunction "(PCINT5/OC1B/MISO/DO/ADC5)PA5_8") (pintype "bidirectional"))
    )
    (net (code "78") (name "Net-(IC11A-RCK)") (class "Default")
      (node (ref "IC11") (pin "12") (pinfunction "RCK_12") (pintype "input"))
      (node (ref "IC1A") (pin "12") (pinfunction "9_12") (pintype "bidirectional"))
      (node (ref "IC1B") (pin "15") (pinfunction "PB1(OC1A)_15") (pintype "bidirectional"))
    )
    (net (code "79") (name "Net-(IC11A-SCK)") (class "Default")
      (node (ref "IC11") (pin "11") (pinfunction "SCK_11") (pintype "input"))
      (node (ref "IC1A") (pin "16") (pinfunction "13_16") (pintype "bidirectional"))
      (node (ref "IC1B") (pin "19") (pinfunction "PB5(SCK)_19") (pintype "bidirectional"))
      (node (ref "IC7") (pin "2") (pinfunction "I_2") (pintype "input"))
    )
    (net (code "80") (name "Net-(JMASTERLED-Pad2)") (class "Default")
      (node (ref "JMASTERLED") (pin "2") (pinfunction "2_2") (pintype "passive"))
      (node (ref "R2") (pin "1") (pinfunction "1_1") (pintype "passive"))
    )
    (net (code "81") (name "Net-(JMASTERLED-Pad4)") (class "Default")
      (node (ref "JMASTERLED") (pin "4") (pinfunction "4_4") (pintype "passive"))
      (node (ref "R1") (pin "1") (pinfunction "1_1") (pintype "passive"))
    )
    (net (code "82") (name "VCC") (class "Default")
      (node (ref "C2") (pin "2") (pinfunction "2_2") (pintype "passive"))
      (node (ref "IC10") (pin "1") (pinfunction "VCC_1") (pintype "bidirectional"))
      (node (ref "IC11") (pin "10") (pinfunction "SCL_10") (pintype "input"))
      (node (ref "IC11") (pin "16") (pinfunction "VCC_16") (pintype "power_in"))
      (node (ref "IC1A") (pin "21") (pinfunction "VCC_21") (pintype "bidirectional"))
      (node (ref "IC1B") (pin "20") (pinfunction "AVCC_20") (pintype "bidirectional"))
      (node (ref "IC1B") (pin "7") (pinfunction "VCC_7") (pintype "bidirectional"))
      (node (ref "IC2") (pin "20") (pinfunction "VCC_20") (pintype "power_in"))
      (node (ref "IC3") (pin "20") (pinfunction "VCC_20") (pintype "power_in"))
      (node (ref "IC4") (pin "20") (pinfunction "VCC_20") (pintype "power_in"))
      (node (ref "IC5") (pin "20") (pinfunction "VCC_20") (pintype "power_in"))
      (node (ref "IC6") (pin "20") (pinfunction "VCC_20") (pintype "bidirectional"))
      (node (ref "IC7") (pin "14") (pinfunction "VCC_14") (pintype "power_in"))
      (node (ref "IC8") (pin "1") (pinfunction "VCC_1") (pintype "bidirectional"))
      (node (ref "IC9") (pin "1") (pinfunction "VCC_1") (pintype "bidirectional"))
      (node (ref "JBUS_CTRL") (pin "2") (pinfunction "2_2") (pintype "passive"))
      (node (ref "JBUS_DRO") (pin "2") (pinfunction "2_2") (pintype "passive"))
      (node (ref "JPOWER") (pin "2") (pinfunction "2_2") (pintype "passive"))
      (node (ref "R3") (pin "2") (pinfunction "2_2") (pintype "passive"))
    )
    (net (code "83") (name "unconnected-(IC1A-4-Pad7)") (class "Default")
      (node (ref "IC1A") (pin "7") (pinfunction "4_7") (pintype "bidirectional"))
    )
    (net (code "84") (name "unconnected-(IC1A-5-Pad8)") (class "Default")
      (node (ref "IC1A") (pin "8") (pinfunction "5_8") (pintype "bidirectional"))
    )
    (net (code "85") (name "unconnected-(IC1A-A0-Pad17)") (class "Default")
      (node (ref "IC1A") (pin "17") (pinfunction "A0_17") (pintype "bidirectional"))
    )
    (net (code "86") (name "unconnected-(IC1A-A1-Pad18)") (class "Default")
      (node (ref "IC1A") (pin "18") (pinfunction "A1_18") (pintype "bidirectional"))
    )
    (net (code "87") (name "unconnected-(IC1A-A2-Pad19)") (class "Default")
      (node (ref "IC1A") (pin "19") (pinfunction "A2_19") (pintype "bidirectional"))
    )
    (net (code "88") (name "unconnected-(IC1A-A3-Pad20)") (class "Default")
      (node (ref "IC1A") (pin "20") (pinfunction "A3_20") (pintype "bidirectional"))
    )
    (net (code "89") (name "unconnected-(IC1A-RAW-Pad24)") (class "Default")
      (node (ref "IC1A") (pin "24") (pinfunction "RAW_24") (pintype "bidirectional"))
    )
    (net (code "90") (name "unconnected-(IC1B-PC0(ADC0)-Pad23)") (class "Default")
      (node (ref "IC1B") (pin "23") (pinfunction "PC0(ADC0)_23") (pintype "bidirectional"))
    )
    (net (code "91") (name "unconnected-(IC1B-PC1(ADC1)-Pad24)") (class "Default")
      (node (ref "IC1B") (pin "24") (pinfunction "PC1(ADC1)_24") (pintype "bidirectional"))
    )
    (net (code "92") (name "unconnected-(IC1B-PC2(ADC2)-Pad25)") (class "Default")
      (node (ref "IC1B") (pin "25") (pinfunction "PC2(ADC2)_25") (pintype "bidirectional"))
    )
    (net (code "93") (name "unconnected-(IC1B-PC3(ADC3)-Pad26)") (class "Default")
      (node (ref "IC1B") (pin "26") (pinfunction "PC3(ADC3)_26") (pintype "bidirectional"))
    )
    (net (code "94") (name "unconnected-(IC1B-PC4(ADC4{slash}SDA)-Pad27)") (class "Default")
      (node (ref "IC1B") (pin "27") (pinfunction "PC4(ADC4/SDA)_27") (pintype "bidirectional"))
    )
    (net (code "95") (name "unconnected-(IC1B-PC5(ADC5{slash}SCL)-Pad28)") (class "Default")
      (node (ref "IC1B") (pin "28") (pinfunction "PC5(ADC5/SCL)_28") (pintype "bidirectional"))
    )
    (net (code "96") (name "unconnected-(IC1B-PD4(XCK{slash}T0)-Pad6)") (class "Default")
      (node (ref "IC1B") (pin "6") (pinfunction "PD4(XCK/T0)_6") (pintype "bidirectional"))
    )
    (net (code "97") (name "unconnected-(IC1B-PD5(T1)-Pad11)") (class "Default")
      (node (ref "IC1B") (pin "11") (pinfunction "PD5(T1)_11") (pintype "bidirectional"))
    )
    (net (code "98") (name "unconnected-(IC8-(PCINT0{slash}AREF{slash}ADC0)PA0-Pad13)") (class "Default")
      (node (ref "IC8") (pin "13") (pinfunction "(PCINT0/AREF/ADC0)PA0_13") (pintype "bidirectional"))
    )
    (net (code "99") (name "unconnected-(IC8-(PCINT1{slash}AIN0{slash}ADC1)PA1-Pad12)") (class "Default")
      (node (ref "IC8") (pin "12") (pinfunction "(PCINT1/AIN0/ADC1)PA1_12") (pintype "bidirectional"))
    )
    (net (code "100") (name "unconnected-(IC9-(PCINT0{slash}AREF{slash}ADC0)PA0-Pad13)") (class "Default")
      (node (ref "IC9") (pin "13") (pinfunction "(PCINT0/AREF/ADC0)PA0_13") (pintype "bidirectional"))
    )
    (net (code "101") (name "unconnected-(IC9-(PCINT1{slash}AIN0{slash}ADC1)PA1-Pad12)") (class "Default")
      (node (ref "IC9") (pin "12") (pinfunction "(PCINT1/AIN0/ADC1)PA1_12") (pintype "bidirectional"))
    )
    (net (code "102") (name "unconnected-(IC10-(PCINT0{slash}AREF{slash}ADC0)PA0-Pad13)") (class "Default")
      (node (ref "IC10") (pin "13") (pinfunction "(PCINT0/AREF/ADC0)PA0_13") (pintype "bidirectional"))
    )
    (net (code "103") (name "unconnected-(IC10-(PCINT1{slash}AIN0{slash}ADC1)PA1-Pad12)") (class "Default")
      (node (ref "IC10") (pin "12") (pinfunction "(PCINT1/AIN0/ADC1)PA1_12") (pintype "bidirectional"))
    )
    (net (code "104") (name "unconnected-(IC11A-QE-Pad4)") (class "Default")
      (node (ref "IC11") (pin "4") (pinfunction "QE_4") (pintype "tri_state"))
    )
    (net (code "105") (name "unconnected-(IC11A-QF-Pad5)") (class "Default")
      (node (ref "IC11") (pin "5") (pinfunction "QF_5") (pintype "tri_state"))
    )
    (net (code "106") (name "unconnected-(IC11A-QG-Pad6)") (class "Default")
      (node (ref "IC11") (pin "6") (pinfunction "QG_6") (pintype "tri_state"))
    )
    (net (code "107") (name "unconnected-(IC11A-QH*-Pad9)") (class "Default")
      (node (ref "IC11") (pin "9") (pinfunction "QH*_9") (pintype "tri_state"))
    )
    (net (code "108") (name "unconnected-(IC11A-QH-Pad7)") (class "Default")
      (node (ref "IC11") (pin "7") (pinfunction "QH_7") (pintype "tri_state"))
    )
    (net (code "109") (name "unconnected-(JBUS_CTRL-Pad4)") (class "Default")
      (node (ref "JBUS_CTRL") (pin "4") (pinfunction "4_4") (pintype "passive"))
    )
    (net (code "110") (name "unconnected-(JBUS_DRO-Pad4)") (class "Default")
      (node (ref "JBUS_DRO") (pin "4") (pinfunction "4_4") (pintype "passive"))
    )
    (net (code "111") (name "unconnected-(JSERIAL-VCC-PadP$4)") (class "Default")
      (node (ref "JSERIAL") (pin "P$4") (pinfunction "VCC_P$4") (pintype "bidirectional"))
    )
  )
)
